# Downconverter.net
KiCad netlist of a schematic drawn in EAGLE
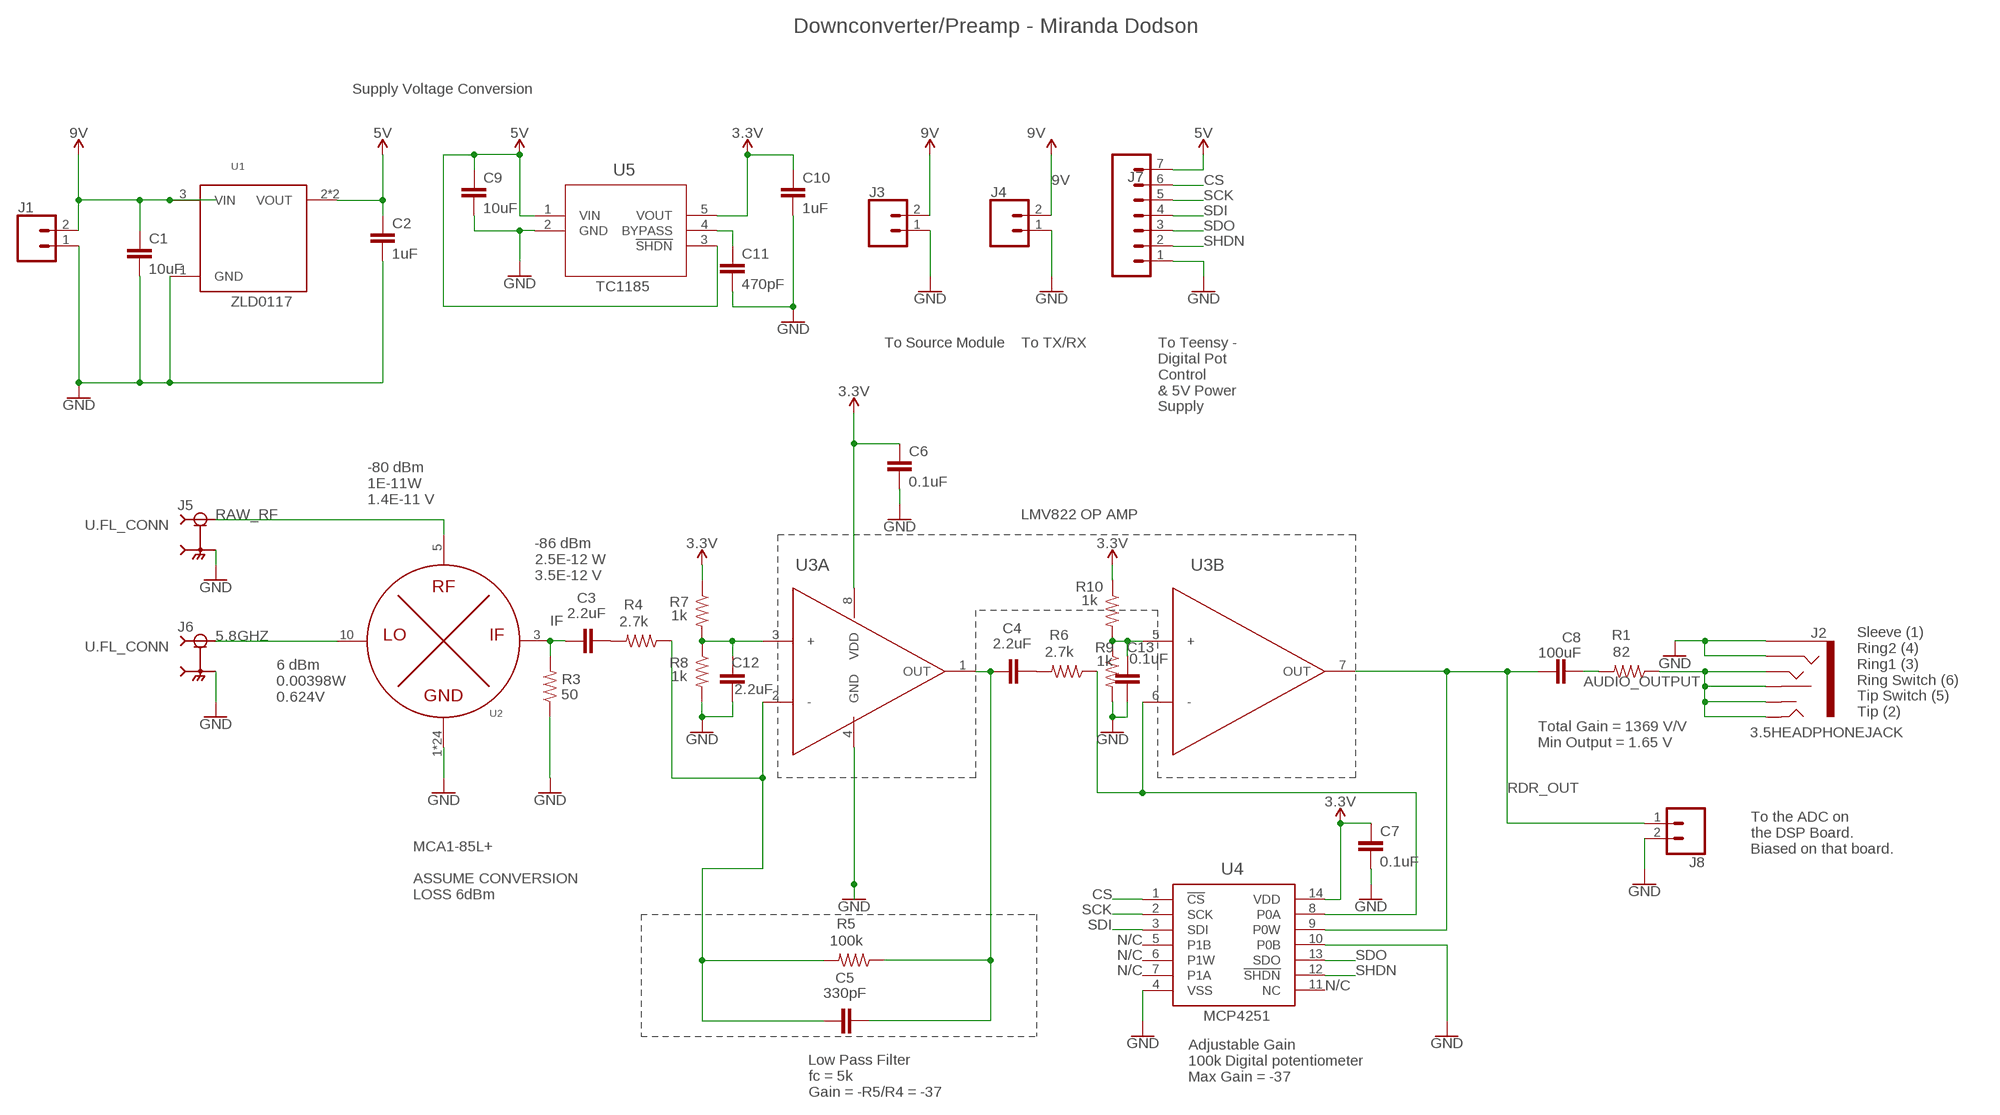
[diagram p0: schematic, sheet 1]

(export (version "E")
  (design (tool "Eeschema 10.0.6"))
  (components
    (comp (ref "C1")
      (value "10uF")
      (footprint "eagle-import:R0603")
      (libsource (lib "eagle-import") (part "C0603"))
    )
    (comp (ref "C2")
      (value "1uF")
      (footprint "eagle-import:R0603")
      (libsource (lib "eagle-import") (part "C0603"))
    )
    (comp (ref "C3")
      (value "2.2uF")
      (footprint "eagle-import:R0603")
      (libsource (lib "eagle-import") (part "C0603"))
    )
    (comp (ref "C4")
      (value "2.2uF")
      (footprint "eagle-import:R0603")
      (libsource (lib "eagle-import") (part "C0603"))
    )
    (comp (ref "C5")
      (value "330pF")
      (footprint "eagle-import:R0603")
      (libsource (lib "eagle-import") (part "C0603"))
    )
    (comp (ref "C6")
      (value "0.1uF")
      (footprint "eagle-import:R0603")
      (libsource (lib "eagle-import") (part "C0603"))
    )
    (comp (ref "C7")
      (value "0.1uF")
      (footprint "eagle-import:R0603")
      (libsource (lib "eagle-import") (part "C0603"))
    )
    (comp (ref "C8")
      (value "100uF")
      (footprint "eagle-import:EXV-9G")
      (fields (field (name "MANUFACTURER_PART_NUMBER") "EDK107M6R3A9GAA"))
      (libsource (lib "eagle-import") (part "EDK107M6R3A9GAA"))
    )
    (comp (ref "C9")
      (value "10uF")
      (footprint "eagle-import:R0603")
      (libsource (lib "eagle-import") (part "C0603"))
    )
    (comp (ref "C10")
      (value "1uF")
      (footprint "eagle-import:R0603")
      (libsource (lib "eagle-import") (part "C0603"))
    )
    (comp (ref "C11")
      (value "470pF")
      (footprint "eagle-import:R0603")
      (libsource (lib "eagle-import") (part "C0603"))
    )
    (comp (ref "C12")
      (value "2.2uF")
      (footprint "eagle-import:R0603")
      (libsource (lib "eagle-import") (part "C0603"))
    )
    (comp (ref "C13")
      (value "0.1uF")
      (footprint "eagle-import:R0603")
      (libsource (lib "eagle-import") (part "C0603"))
    )
    (comp (ref "J1")
      (value "CONN_02")
      (footprint "eagle-import:1X02")
      (libsource (lib "eagle-import") (part "CONN_02"))
    )
    (comp (ref "J2")
      (value "3.5HEADPHONEJACK")
      (footprint "eagle-import:CONN6_SJ-43516-SMT")
      (libsource (lib "eagle-import") (part "3.5HEADPHONEJACK"))
    )
    (comp (ref "J3")
      (value "CONN_02")
      (footprint "eagle-import:1X02")
      (libsource (lib "eagle-import") (part "CONN_02"))
    )
    (comp (ref "J4")
      (value "CONN_02")
      (footprint "eagle-import:1X02")
      (libsource (lib "eagle-import") (part "CONN_02"))
    )
    (comp (ref "J5")
      (value "U.FL_CONN")
      (footprint "eagle-import:U.FL")
      (fields (field (name "MF") "Hirose") (field (name "MP") "U.FL-R-SMT_10_"))
      (libsource (lib "eagle-import") (part "U.FL_CONN"))
    )
    (comp (ref "J6")
      (value "U.FL_CONN")
      (footprint "eagle-import:U.FL")
      (fields (field (name "MF") "Hirose") (field (name "MP") "U.FL-R-SMT_10_"))
      (libsource (lib "eagle-import") (part "U.FL_CONN"))
    )
    (comp (ref "J7")
      (value "CONN_07")
      (footprint "eagle-import:1X07")
      (libsource (lib "eagle-import") (part "CONN_07"))
    )
    (comp (ref "J8")
      (value "CONN_02")
      (footprint "eagle-import:1X02")
      (libsource (lib "eagle-import") (part "CONN_02"))
    )
    (comp (ref "R1")
      (value "82")
      (footprint "eagle-import:R0603")
      (libsource (lib "eagle-import") (part "R0603"))
    )
    (comp (ref "R3")
      (value "50")
      (footprint "eagle-import:R0603")
      (libsource (lib "eagle-import") (part "R0603"))
    )
    (comp (ref "R4")
      (value "2.7k")
      (footprint "eagle-import:R0603")
      (libsource (lib "eagle-import") (part "R0603"))
    )
    (comp (ref "R5")
      (value "100k")
      (footprint "eagle-import:R0603")
      (libsource (lib "eagle-import") (part "R0603"))
    )
    (comp (ref "R6")
      (value "2.7k")
      (footprint "eagle-import:R0603")
      (libsource (lib "eagle-import") (part "R0603"))
    )
    (comp (ref "R7")
      (value "1k")
      (footprint "eagle-import:R0603")
      (libsource (lib "eagle-import") (part "R0603"))
    )
    (comp (ref "R8")
      (value "1k")
      (footprint "eagle-import:R0603")
      (libsource (lib "eagle-import") (part "R0603"))
    )
    (comp (ref "R9")
      (value "1k")
      (footprint "eagle-import:R0603")
      (libsource (lib "eagle-import") (part "R0603"))
    )
    (comp (ref "R10")
      (value "1k")
      (footprint "eagle-import:R0603")
      (libsource (lib "eagle-import") (part "R0603"))
    )
    (comp (ref "U1")
      (value "5V_REG")
      (footprint "eagle-import:5V_REG")
      (libsource (lib "eagle-import") (part "5V_REG"))
    )
    (comp (ref "U2")
      (value "MIXER")
      (footprint "eagle-import:MIXER")
      (libsource (lib "eagle-import") (part "MIXER"))
    )
    (comp (ref "U3")
      (value "DUAL_OP_AMP_LMV822")
      (footprint "eagle-import:M08A")
      (libsource (lib "eagle-import") (part "DUAL_OP_AMP_LMV822"))
    )
    (comp (ref "U4")
      (value "DIGITAL_POTDIGITAL_POT")
      (footprint "eagle-import:DIGITAL_POT")
      (libsource (lib "eagle-import") (part "DIGITAL_POTDIGITAL_POT"))
    )
    (comp (ref "U5")
      (value "TC1185-3.3VCT713")
      (footprint "eagle-import:SOT-23-5_MC")
      (fields (field (name "MANUFACTURER_PART_NUMBER") "TC11853.3VCT713"))
      (libsource (lib "eagle-import") (part "TC1185-3.3VCT713"))
    )
  )
  (nets
    (net (code "1") (name "/5.8GHZ") (class "Default")
      (node (ref "J6") (pin "1") (pinfunction "SIG_1") (pintype "passive"))
      (node (ref "U2") (pin "10") (pinfunction "LO_10") (pintype "passive"))
    )
    (net (code "2") (name "/AUDIO_OUTPUT") (class "Default")
      (node (ref "J2") (pin "3") (pinfunction "RINGSWITCH_3") (pintype "bidirectional"))
      (node (ref "J2") (pin "4") (pinfunction "RING1_4") (pintype "bidirectional"))
      (node (ref "J2") (pin "7") (pinfunction "TIPSWITCH_7") (pintype "bidirectional"))
      (node (ref "J2") (pin "8") (pinfunction "TIP_8") (pintype "bidirectional"))
      (node (ref "R1") (pin "1") (pinfunction "1_1") (pintype "passive"))
    )
    (net (code "3") (name "/CS") (class "Default")
      (node (ref "J7") (pin "6") (pinfunction "6_6") (pintype "passive"))
      (node (ref "U4") (pin "1") (pinfunction "~{CS}_1") (pintype "passive"))
    )
    (net (code "4") (name "/IF") (class "Default")
      (node (ref "C3") (pin "1") (pinfunction "1_1") (pintype "passive"))
      (node (ref "R3") (pin "2") (pinfunction "2_2") (pintype "passive"))
      (node (ref "U2") (pin "3") (pinfunction "IF_3") (pintype "passive"))
    )
    (net (code "5") (name "/RAW_RF") (class "Default")
      (node (ref "J5") (pin "1") (pinfunction "SIG_1") (pintype "passive"))
      (node (ref "U2") (pin "5") (pinfunction "RF_5") (pintype "passive"))
    )
    (net (code "6") (name "/RDR_OUT") (class "Default")
      (node (ref "C8") (pin "1") (pinfunction "1_1") (pintype "passive"))
      (node (ref "J8") (pin "1") (pinfunction "1_1") (pintype "passive"))
      (node (ref "U3") (pin "7") (pinfunction "OUT_7") (pintype "passive"))
      (node (ref "U4") (pin "9") (pinfunction "P0W_9") (pintype "passive"))
    )
    (net (code "7") (name "/SCK") (class "Default")
      (node (ref "J7") (pin "5") (pinfunction "5_5") (pintype "passive"))
      (node (ref "U4") (pin "2") (pinfunction "SCK_2") (pintype "passive"))
    )
    (net (code "8") (name "/SDI") (class "Default")
      (node (ref "J7") (pin "4") (pinfunction "4_4") (pintype "passive"))
      (node (ref "U4") (pin "3") (pinfunction "SDI_3") (pintype "passive"))
    )
    (net (code "9") (name "/SDO") (class "Default")
      (node (ref "J7") (pin "3") (pinfunction "3_3") (pintype "passive"))
      (node (ref "U4") (pin "13") (pinfunction "SDO_13") (pintype "passive"))
    )
    (net (code "10") (name "/SHDN") (class "Default")
      (node (ref "J7") (pin "2") (pinfunction "2_2") (pintype "passive"))
      (node (ref "U4") (pin "12") (pinfunction "~{SHDN}_12") (pintype "passive"))
    )
    (net (code "11") (name "3.3V") (class "Default")
      (node (ref "C10") (pin "1") (pinfunction "1_1") (pintype "passive"))
      (node (ref "C6") (pin "1") (pinfunction "1_1") (pintype "passive"))
      (node (ref "C7") (pin "1") (pinfunction "1_1") (pintype "passive"))
      (node (ref "R10") (pin "1") (pinfunction "1_1") (pintype "passive"))
      (node (ref "R7") (pin "1") (pinfunction "1_1") (pintype "passive"))
      (node (ref "U3") (pin "8") (pinfunction "VDD_8") (pintype "passive"))
      (node (ref "U4") (pin "14") (pinfunction "VDD_14") (pintype "passive"))
      (node (ref "U5") (pin "5") (pinfunction "VOUT_5") (pintype "bidirectional"))
    )
    (net (code "12") (name "5V") (class "Default")
      (node (ref "C2") (pin "1") (pinfunction "1_1") (pintype "passive"))
      (node (ref "C9") (pin "1") (pinfunction "1_1") (pintype "passive"))
      (node (ref "J7") (pin "7") (pinfunction "7_7") (pintype "passive"))
      (node (ref "U1") (pin "2") (pinfunction "VOUT_2") (pintype "bidirectional"))
      (node (ref "U1") (pin "4") (pinfunction "VOUT_4") (pintype "bidirectional"))
      (node (ref "U5") (pin "1") (pinfunction "VIN_1") (pintype "input"))
      (node (ref "U5") (pin "3") (pinfunction "~{SHDN}_3") (pintype "input"))
    )
    (net (code "13") (name "9V") (class "Default")
      (node (ref "C1") (pin "1") (pinfunction "1_1") (pintype "passive"))
      (node (ref "J1") (pin "2") (pinfunction "2_2") (pintype "passive"))
      (node (ref "J3") (pin "2") (pinfunction "2_2") (pintype "passive"))
      (node (ref "J4") (pin "2") (pinfunction "2_2") (pintype "passive"))
      (node (ref "U1") (pin "3") (pinfunction "VIN_3") (pintype "bidirectional"))
    )
    (net (code "14") (name "GND") (class "Default")
      (node (ref "C1") (pin "2") (pinfunction "2_2") (pintype "passive"))
      (node (ref "C10") (pin "2") (pinfunction "2_2") (pintype "passive"))
      (node (ref "C11") (pin "2") (pinfunction "2_2") (pintype "passive"))
      (node (ref "C12") (pin "2") (pinfunction "2_2") (pintype "passive"))
      (node (ref "C13") (pin "2") (pinfunction "2_2") (pintype "passive"))
      (node (ref "C2") (pin "2") (pinfunction "2_2") (pintype "passive"))
      (node (ref "C6") (pin "2") (pinfunction "2_2") (pintype "passive"))
      (node (ref "C7") (pin "2") (pinfunction "2_2") (pintype "passive"))
      (node (ref "C9") (pin "2") (pinfunction "2_2") (pintype "passive"))
      (node (ref "J1") (pin "1") (pinfunction "1_1") (pintype "passive"))
      (node (ref "J2") (pin "1") (pinfunction "SLEEVE_1") (pintype "bidirectional"))
      (node (ref "J2") (pin "2") (pinfunction "RING2_2") (pintype "bidirectional"))
      (node (ref "J3") (pin "1") (pinfunction "1_1") (pintype "passive"))
      (node (ref "J4") (pin "1") (pinfunction "1_1") (pintype "passive"))
      (node (ref "J5") (pin "2") (pinfunction "GND_2") (pintype "passive"))
      (node (ref "J5") (pin "3") (pinfunction "GND_3") (pintype "passive"))
      (node (ref "J6") (pin "2") (pinfunction "GND_2") (pintype "passive"))
      (node (ref "J6") (pin "3") (pinfunction "GND_3") (pintype "passive"))
      (node (ref "J7") (pin "1") (pinfunction "1_1") (pintype "passive"))
      (node (ref "J8") (pin "2") (pinfunction "2_2") (pintype "passive"))
      (node (ref "R3") (pin "1") (pinfunction "1_1") (pintype "passive"))
      (node (ref "R8") (pin "2") (pinfunction "2_2") (pintype "passive"))
      (node (ref "R9") (pin "2") (pinfunction "2_2") (pintype "passive"))
      (node (ref "U1") (pin "1") (pinfunction "GND_1") (pintype "bidirectional"))
      (node (ref "U2") (pin "1") (pinfunction "GND_1") (pintype "passive"))
      (node (ref "U2") (pin "2") (pinfunction "GND_2") (pintype "passive"))
      (node (ref "U2") (pin "4") (pinfunction "GND_4") (pintype "passive"))
      (node (ref "U2") (pin "6") (pinfunction "GND_6") (pintype "passive"))
      (node (ref "U2") (pin "7") (pinfunction "GND_7") (pintype "passive"))
      (node (ref "U2") (pin "8") (pinfunction "GND_8") (pintype "passive"))
      (node (ref "U2") (pin "9") (pinfunction "GND_9") (pintype "passive"))
      (node (ref "U2") (pin "P$1") (pinfunction "GND_P$1") (pintype "passive"))
      (node (ref "U2") (pin "P$10") (pinfunction "GND_P$10") (pintype "passive"))
      (node (ref "U2") (pin "P$11") (pinfunction "GND_P$11") (pintype "passive"))
      (node (ref "U2") (pin "P$12") (pinfunction "GND_P$12") (pintype "passive"))
      (node (ref "U2") (pin "P$13") (pinfunction "GND_P$13") (pintype "passive"))
      (node (ref "U2") (pin "P$14") (pinfunction "GND_P$14") (pintype "passive"))
      (node (ref "U2") (pin "P$15") (pinfunction "GND_P$15") (pintype "passive"))
      (node (ref "U2") (pin "P$16") (pinfunction "GND_P$16") (pintype "passive"))
      (node (ref "U2") (pin "P$17") (pinfunction "GND_P$17") (pintype "passive"))
      (node (ref "U2") (pin "P$2") (pinfunction "GND_P$2") (pintype "passive"))
      (node (ref "U2") (pin "P$3") (pinfunction "GND_P$3") (pintype "passive"))
      (node (ref "U2") (pin "P$4") (pinfunction "GND_P$4") (pintype "passive"))
      (node (ref "U2") (pin "P$5") (pinfunction "GND_P$5") (pintype "passive"))
      (node (ref "U2") (pin "P$6") (pinfunction "GND_P$6") (pintype "passive"))
      (node (ref "U2") (pin "P$7") (pinfunction "GND_P$7") (pintype "passive"))
      (node (ref "U2") (pin "P$8") (pinfunction "GND_P$8") (pintype "passive"))
      (node (ref "U2") (pin "P$9") (pinfunction "GND_P$9") (pintype "passive"))
      (node (ref "U3") (pin "4") (pinfunction "GND_4") (pintype "passive"))
      (node (ref "U4") (pin "10") (pinfunction "P0B_10") (pintype "passive"))
      (node (ref "U4") (pin "4") (pinfunction "VSS_4") (pintype "passive"))
      (node (ref "U5") (pin "2") (pinfunction "GND_2") (pintype "bidirectional"))
    )
    (net (code "15") (name "Net-(C3-Pad2)") (class "Default")
      (node (ref "C3") (pin "2") (pinfunction "2_2") (pintype "passive"))
      (node (ref "R4") (pin "2") (pinfunction "2_2") (pintype "passive"))
    )
    (net (code "16") (name "Net-(C4-Pad2)") (class "Default")
      (node (ref "C4") (pin "2") (pinfunction "2_2") (pintype "passive"))
      (node (ref "R6") (pin "2") (pinfunction "2_2") (pintype "passive"))
    )
    (net (code "17") (name "Net-(C8-Pad2)") (class "Default")
      (node (ref "C8") (pin "2") (pinfunction "2_2") (pintype "passive"))
      (node (ref "R1") (pin "2") (pinfunction "2_2") (pintype "passive"))
    )
    (net (code "18") (name "Net-(U3A-+)") (class "Default")
      (node (ref "C12") (pin "1") (pinfunction "1_1") (pintype "passive"))
      (node (ref "R7") (pin "2") (pinfunction "2_2") (pintype "passive"))
      (node (ref "R8") (pin "1") (pinfunction "1_1") (pintype "passive"))
      (node (ref "U3") (pin "3") (pinfunction "+_3") (pintype "passive"))
    )
    (net (code "19") (name "Net-(U3A--)") (class "Default")
      (node (ref "C5") (pin "1") (pinfunction "1_1") (pintype "passive"))
      (node (ref "R4") (pin "1") (pinfunction "1_1") (pintype "passive"))
      (node (ref "R5") (pin "2") (pinfunction "2_2") (pintype "passive"))
      (node (ref "U3") (pin "2") (pinfunction "-_2") (pintype "passive"))
    )
    (net (code "20") (name "Net-(U3A-OUT)") (class "Default")
      (node (ref "C4") (pin "1") (pinfunction "1_1") (pintype "passive"))
      (node (ref "C5") (pin "2") (pinfunction "2_2") (pintype "passive"))
      (node (ref "R5") (pin "1") (pinfunction "1_1") (pintype "passive"))
      (node (ref "U3") (pin "1") (pinfunction "OUT_1") (pintype "passive"))
    )
    (net (code "21") (name "Net-(U3B-+)") (class "Default")
      (node (ref "C13") (pin "1") (pinfunction "1_1") (pintype "passive"))
      (node (ref "R10") (pin "2") (pinfunction "2_2") (pintype "passive"))
      (node (ref "R9") (pin "1") (pinfunction "1_1") (pintype "passive"))
      (node (ref "U3") (pin "5") (pinfunction "+_5") (pintype "passive"))
    )
    (net (code "22") (name "Net-(U3B--)") (class "Default")
      (node (ref "R6") (pin "1") (pinfunction "1_1") (pintype "passive"))
      (node (ref "U3") (pin "6") (pinfunction "-_6") (pintype "passive"))
      (node (ref "U4") (pin "8") (pinfunction "P0A_8") (pintype "passive"))
    )
    (net (code "23") (name "Net-(U5-BYPASS)") (class "Default")
      (node (ref "C11") (pin "1") (pinfunction "1_1") (pintype "passive"))
      (node (ref "U5") (pin "4") (pinfunction "BYPASS_4") (pintype "input"))
    )
    (net (code "24") (name "unconnected-(U4-NC-Pad11)") (class "Default")
      (node (ref "U4") (pin "11") (pinfunction "NC_11") (pintype "passive"))
    )
    (net (code "25") (name "unconnected-(U4-P1A-Pad7)") (class "Default")
      (node (ref "U4") (pin "7") (pinfunction "P1A_7") (pintype "passive"))
    )
    (net (code "26") (name "unconnected-(U4-P1B-Pad5)") (class "Default")
      (node (ref "U4") (pin "5") (pinfunction "P1B_5") (pintype "passive"))
    )
    (net (code "27") (name "unconnected-(U4-P1W-Pad6)") (class "Default")
      (node (ref "U4") (pin "6") (pinfunction "P1W_6") (pintype "passive"))
    )
  )
)
